# LEDSlave_1.net
KiCad netlist of a schematic drawn in EAGLE
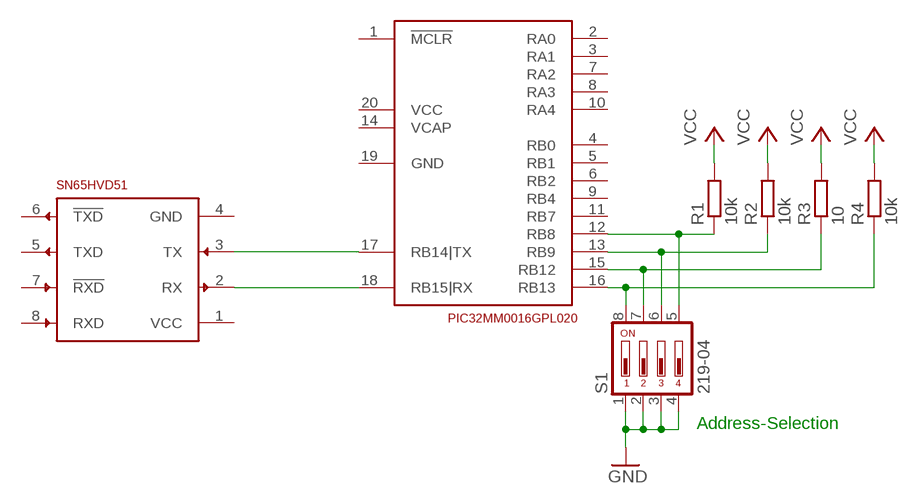
[diagram p0: schematic, sheet 1]

(export (version "E")
  (design (tool "Eeschema 10.0.6"))
  (components
    (comp (ref "R1")
      (value "10k")
      (footprint "eagle-import:R0805")
      (libsource (lib "eagle-import") (part "R-EU_R0805"))
    )
    (comp (ref "R2")
      (value "10k")
      (footprint "eagle-import:R0805")
      (libsource (lib "eagle-import") (part "R-EU_R0805"))
    )
    (comp (ref "R3")
      (value "10")
      (footprint "eagle-import:R0805")
      (libsource (lib "eagle-import") (part "R-EU_R0805"))
    )
    (comp (ref "R4")
      (value "10k")
      (footprint "eagle-import:R0805")
      (libsource (lib "eagle-import") (part "R-EU_R0805"))
    )
    (comp (ref "S1")
      (value "219-04")
      (footprint "eagle-import:CTS-219-04")
      (libsource (lib "eagle-import") (part "219-04"))
    )
    (comp (ref "U$1")
      (value "PIC32MM0016GPL020")
      (footprint "eagle-import:SSOP20")
      (libsource (lib "eagle-import") (part "PIC32MM0016GPL020"))
    )
    (comp (ref "U$2")
      (value "SN65HVD51")
      (footprint "eagle-import:SO-08")
      (libsource (lib "eagle-import") (part "SN65HVD51"))
    )
  )
  (nets
    (net (code "1") (name "GND") (class "Default")
      (node (ref "S1") (pin "1") (pinfunction "1_1") (pintype "passive"))
      (node (ref "S1") (pin "2") (pinfunction "2_2") (pintype "passive"))
      (node (ref "S1") (pin "3") (pinfunction "3_3") (pintype "passive"))
      (node (ref "S1") (pin "4") (pinfunction "4_4") (pintype "passive"))
    )
    (net (code "2") (name "Net-(U$1-RB8)") (class "Default")
      (node (ref "R1") (pin "1") (pinfunction "1_1") (pintype "passive"))
      (node (ref "S1") (pin "5") (pinfunction "5_5") (pintype "passive"))
      (node (ref "U$1") (pin "12") (pinfunction "RB8_12") (pintype "bidirectional"))
    )
    (net (code "3") (name "Net-(U$1-RB9)") (class "Default")
      (node (ref "R2") (pin "1") (pinfunction "1_1") (pintype "passive"))
      (node (ref "S1") (pin "6") (pinfunction "6_6") (pintype "passive"))
      (node (ref "U$1") (pin "13") (pinfunction "RB9_13") (pintype "bidirectional"))
    )
    (net (code "4") (name "Net-(U$1-RB12)") (class "Default")
      (node (ref "R3") (pin "1") (pinfunction "1_1") (pintype "passive"))
      (node (ref "S1") (pin "7") (pinfunction "7_7") (pintype "passive"))
      (node (ref "U$1") (pin "15") (pinfunction "RB12_15") (pintype "bidirectional"))
    )
    (net (code "5") (name "Net-(U$1-RB13)") (class "Default")
      (node (ref "R4") (pin "1") (pinfunction "1_1") (pintype "passive"))
      (node (ref "S1") (pin "8") (pinfunction "8_8") (pintype "passive"))
      (node (ref "U$1") (pin "16") (pinfunction "RB13_16") (pintype "bidirectional"))
    )
    (net (code "6") (name "Net-(U$1-RB14|TX)") (class "Default")
      (node (ref "U$1") (pin "17") (pinfunction "RB14|TX_17") (pintype "bidirectional"))
      (node (ref "U$2") (pin "3") (pinfunction "TX_3") (pintype "bidirectional"))
    )
    (net (code "7") (name "Net-(U$1-RB15|RX)") (class "Default")
      (node (ref "U$1") (pin "18") (pinfunction "RB15|RX_18") (pintype "bidirectional"))
      (node (ref "U$2") (pin "2") (pinfunction "RX_2") (pintype "bidirectional"))
    )
    (net (code "8") (name "VCC") (class "Default")
      (node (ref "R1") (pin "2") (pinfunction "2_2") (pintype "passive"))
      (node (ref "R2") (pin "2") (pinfunction "2_2") (pintype "passive"))
      (node (ref "R3") (pin "2") (pinfunction "2_2") (pintype "passive"))
      (node (ref "R4") (pin "2") (pinfunction "2_2") (pintype "passive"))
    )
    (net (code "9") (name "unconnected-(U$1-GND-Pad19)") (class "Default")
      (node (ref "U$1") (pin "19") (pinfunction "GND_19") (pintype "bidirectional"))
    )
    (net (code "10") (name "unconnected-(U$1-RA0-Pad2)") (class "Default")
      (node (ref "U$1") (pin "2") (pinfunction "RA0_2") (pintype "bidirectional"))
    )
    (net (code "11") (name "unconnected-(U$1-RA1-Pad3)") (class "Default")
      (node (ref "U$1") (pin "3") (pinfunction "RA1_3") (pintype "bidirectional"))
    )
    (net (code "12") (name "unconnected-(U$1-RA2-Pad7)") (class "Default")
      (node (ref "U$1") (pin "7") (pinfunction "RA2_7") (pintype "bidirectional"))
    )
    (net (code "13") (name "unconnected-(U$1-RA3-Pad8)") (class "Default")
      (node (ref "U$1") (pin "8") (pinfunction "RA3_8") (pintype "bidirectional"))
    )
    (net (code "14") (name "unconnected-(U$1-RA4-Pad10)") (class "Default")
      (node (ref "U$1") (pin "10") (pinfunction "RA4_10") (pintype "bidirectional"))
    )
    (net (code "15") (name "unconnected-(U$1-RB0-Pad4)") (class "Default")
      (node (ref "U$1") (pin "4") (pinfunction "RB0_4") (pintype "bidirectional"))
    )
    (net (code "16") (name "unconnected-(U$1-RB1-Pad5)") (class "Default")
      (node (ref "U$1") (pin "5") (pinfunction "RB1_5") (pintype "bidirectional"))
    )
    (net (code "17") (name "unconnected-(U$1-RB2-Pad6)") (class "Default")
      (node (ref "U$1") (pin "6") (pinfunction "RB2_6") (pintype "bidirectional"))
    )
    (net (code "18") (name "unconnected-(U$1-RB4-Pad9)") (class "Default")
      (node (ref "U$1") (pin "9") (pinfunction "RB4_9") (pintype "bidirectional"))
    )
    (net (code "19") (name "unconnected-(U$1-RB7-Pad11)") (class "Default")
      (node (ref "U$1") (pin "11") (pinfunction "RB7_11") (pintype "bidirectional"))
    )
    (net (code "20") (name "unconnected-(U$1-VCAP-Pad14)") (class "Default")
      (node (ref "U$1") (pin "14") (pinfunction "VCAP_14") (pintype "bidirectional"))
    )
    (net (code "21") (name "unconnected-(U$1-VCC-Pad20)") (class "Default")
      (node (ref "U$1") (pin "20") (pinfunction "VCC_20") (pintype "bidirectional"))
    )
    (net (code "22") (name "unconnected-(U$1-~{MCLR}-Pad1)") (class "Default")
      (node (ref "U$1") (pin "1") (pinfunction "~{MCLR}_1") (pintype "bidirectional"))
    )
    (net (code "23") (name "unconnected-(U$2-GND-Pad4)") (class "Default")
      (node (ref "U$2") (pin "4") (pinfunction "GND_4") (pintype "bidirectional"))
    )
    (net (code "24") (name "unconnected-(U$2-RXD-Pad8)") (class "Default")
      (node (ref "U$2") (pin "8") (pinfunction "RXD_8") (pintype "bidirectional"))
    )
    (net (code "25") (name "unconnected-(U$2-TXD-Pad5)") (class "Default")
      (node (ref "U$2") (pin "5") (pinfunction "TXD_5") (pintype "bidirectional"))
    )
    (net (code "26") (name "unconnected-(U$2-VCC-Pad1)") (class "Default")
      (node (ref "U$2") (pin "1") (pinfunction "VCC_1") (pintype "bidirectional"))
    )
    (net (code "27") (name "unconnected-(U$2-~{RXD}-Pad7)") (class "Default")
      (node (ref "U$2") (pin "7") (pinfunction "~{RXD}_7") (pintype "bidirectional"))
    )
    (net (code "28") (name "unconnected-(U$2-~{TXD}-Pad6)") (class "Default")
      (node (ref "U$2") (pin "6") (pinfunction "~{TXD}_6") (pintype "bidirectional"))
    )
  )
)
